# POWERREG.net
KiCad netlist of a schematic drawn in Altium Designer
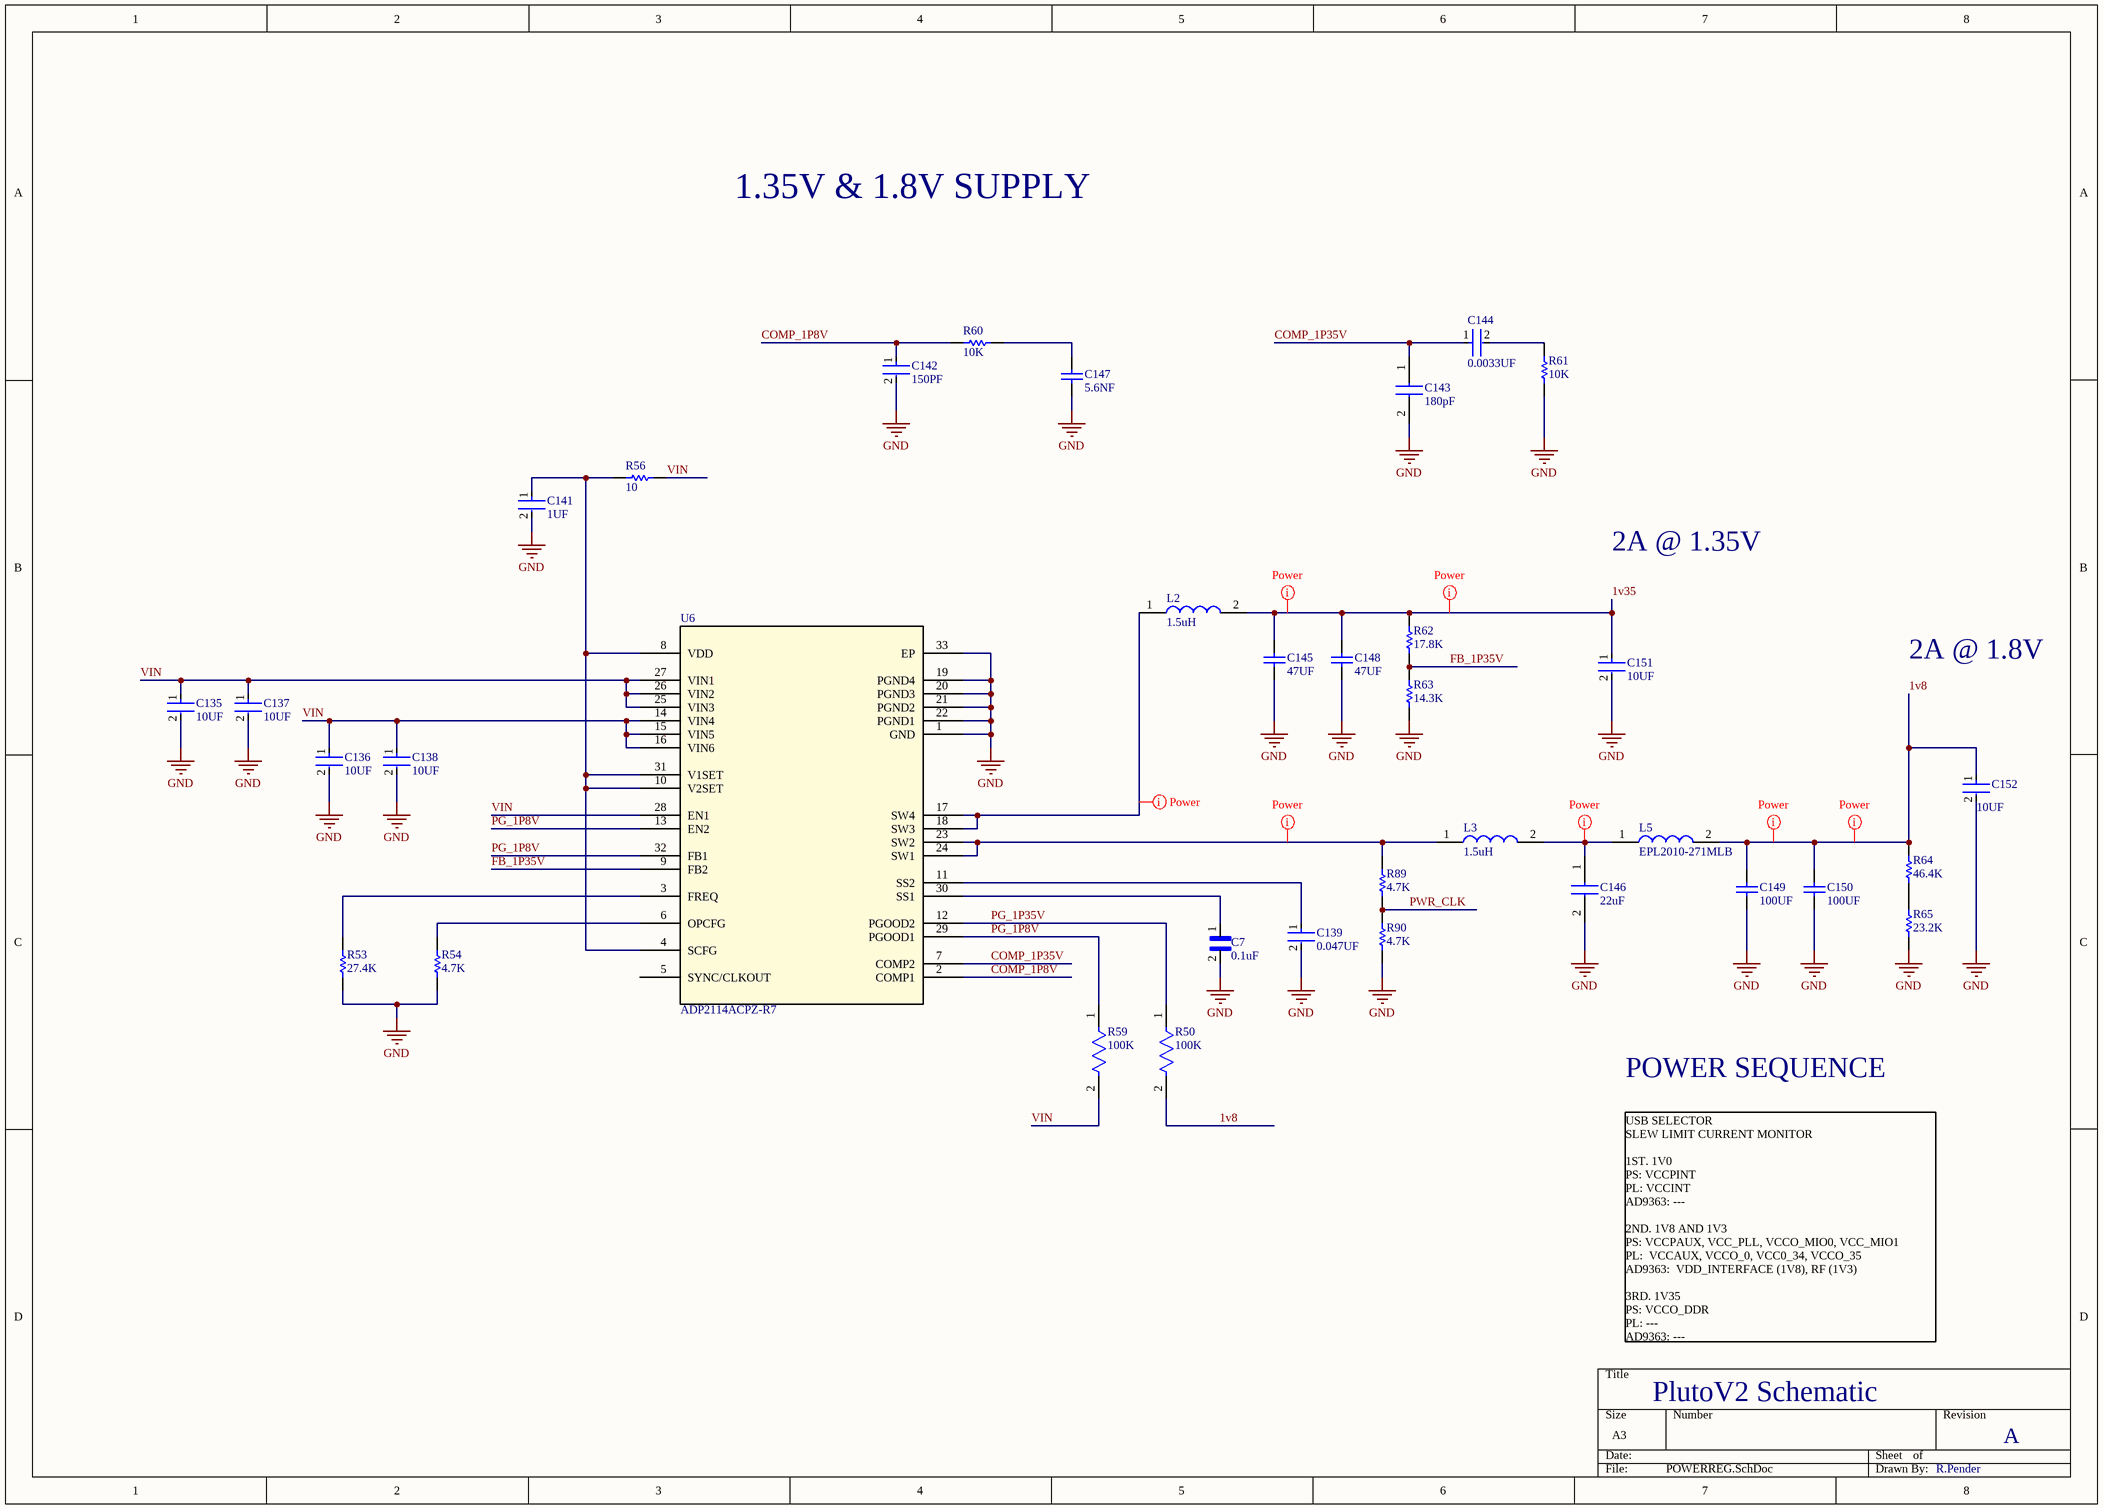
[diagram p0: POWERREG.SchDoc]

(export (version "E")
  (design (tool "Eeschema 10.0.6"))
  (components
    (comp (ref "C7")
      (value "0.1uF")
      (footprint "CAPC0603X33N")
      (description "CAP 0.1UF 16VDC X5R 20% SMD 0201 PAPER TAPE")
      (fields (field (name "MP") "GRM033R61C104ME84D"))
      (libsource (lib "GRM033R61C104ME84D") (part "GRM033R61C104ME84D"))
    )
    (comp (ref "C135")
      (value "10UF")
      (footprint "FP-GRM188-0_15-MFG")
      (description "Chip Multilayer Ceramic Capacitors for General Purpose, 0603, 10uF, X5R, 15%, 20%, 10V")
      (fields (field (name "TOLERANCE") "20%"))
      (libsource (lib "Altium Content Vault") (part "02cd4be3c70576c341d710602a673aa"))
    )
    (comp (ref "C136")
      (value "10UF")
      (footprint "FP-GRM188-0_15-MFG")
      (description "Chip Multilayer Ceramic Capacitors for General Purpose, 0603, 10uF, X5R, 15%, 20%, 10V")
      (fields (field (name "TOLERANCE") "20%"))
      (libsource (lib "Altium Content Vault") (part "02cd4be3c70576c341d710602a673aa"))
    )
    (comp (ref "C137")
      (value "10UF")
      (footprint "FP-GRM188-0_15-MFG")
      (description "Chip Multilayer Ceramic Capacitors for General Purpose, 0603, 10uF, X5R, 15%, 20%, 10V")
      (fields (field (name "TOLERANCE") "20%"))
      (libsource (lib "Altium Content Vault") (part "02cd4be3c70576c341d710602a673aa"))
    )
    (comp (ref "C138")
      (value "10UF")
      (footprint "FP-GRM188-0_15-MFG")
      (description "Chip Multilayer Ceramic Capacitors for General Purpose, 0603, 10uF, X5R, 15%, 20%, 10V")
      (fields (field (name "TOLERANCE") "20%"))
      (libsource (lib "Altium Content Vault") (part "02cd4be3c70576c341d710602a673aa"))
    )
    (comp (ref "C139")
      (value "0.047UF")
      (footprint "FP-GCM155-0_05-IPC_C")
      (description "Ceramic Capacitor for Automotive 47nF ±10% 25VDC X7R 0402 Paper T/R")
      (fields (field (name "VOLTAGE") "25V") (field (name "TOLERANCE") "10%"))
      (libsource (lib "Altium Content Vault") (part "02cd4be3c70576c341d710602a673aa"))
    )
    (comp (ref "C141")
      (value "1UF")
      (footprint "FP-0402-L_1_0_0_05-W_0_5-IPC_A")
      (description "None")
      (fields (field (name "TOLERANCE") "10%"))
      (libsource (lib "Altium Content Vault") (part "b4654b650e69147ec39a6b967a45e02"))
    )
    (comp (ref "C142")
      (value "150PF")
      (footprint "FP-GCM155-0_05-IPC_C")
      (description "Ceramic Capacitor for Automotive 150pF ±1% 50VDC C0G 0402 Paper T/R")
      (libsource (lib "Altium Content Vault") (part "02cd4be3c70576c341d710602a673aa"))
    )
    (comp (ref "C143")
      (value "180pF")
      (footprint "SamacSys:CAPC1005X55N")
      (description "Capacitor")
      (fields (field (name "MANUFACTURER_PART_NUMBER") "CGJ2B2C0G1H181J050BA"))
      (libsource (lib "SamacSys") (part "CGJ2B2C0G1H181J050BA"))
    )
    (comp (ref "C144")
      (value "0.0033UF")
      (footprint "FP-CC0402-MFG")
      (description "CAP CER 3300PF 50V X7R 0402")
      (fields
        (field (name "OCTOPART") "https://octopart.com/cc0402krx7r9bb332-yageo-192887")
        (field (name "MANUFACTURER") "YAGEO")
      )
      (libsource (lib "Altium Content Vault") (part "11868f565c42a9108669ba33697ecf6"))
    )
    (comp (ref "C145")
      (value "47UF")
      (footprint "TAYO-JMK212BBJ476MG-T_L")
      (fields
        (field (name "MANUFACTURER") "Taiyo Yuden")
        (field (name "TOLERANCE") "±20%")
        (field (name "PCN PART NUMBER") "X5R,X7RDielectrics23/Jan/2008")
      )
      (libsource (lib "Altium Content Vault") (part "CAP-NP-2"))
    )
    (comp (ref "C146")
      (value "22uF")
      (footprint "SamacSys:CAPC2012X95N")
      (description "Capacitor")
      (fields (field (name "MANUFACTURER_PART_NUMBER") "CL21A226KPCLRNC"))
      (libsource (lib "SamacSys") (part "CL21A226KPCLRNC"))
    )
    (comp (ref "C147")
      (value "5.6NF")
      (footprint "CAPC1005X56X25NL10T15")
      (fields
        (field (name "MANUFACTURER") "AVX Interconnect / Elco")
        (field (name "PART NUMBER") "04025C562JAT2A")
      )
      (libsource (lib "Altium Content Vault") (part "CAP"))
    )
    (comp (ref "C148")
      (value "47UF")
      (footprint "TAYO-JMK212BBJ476MG-T_L")
      (fields
        (field (name "MANUFACTURER") "Taiyo Yuden")
        (field (name "TOLERANCE") "±20%")
        (field (name "PCN PART NUMBER") "X5R,X7RDielectrics23/Jan/2008")
      )
      (libsource (lib "Altium Content Vault") (part "CAP-NP-2"))
    )
    (comp (ref "C149")
      (value "100UF")
      (footprint "CAPC3216X190X55ML30T25")
      (description "Chip Capacitor, 100 uF, +/- 20%, 6.3 V, -55 to 85 degC, 1206 (3216 Metric), RoHS, Tape and Reel")
      (fields (field (name "TOLERANCE") "20%") (field (name "PARTNUMBER") "GRM31CR60J107ME39L"))
      (libsource (lib "Altium Content Vault") (part "CAP-NP-2"))
    )
    (comp (ref "C150")
      (value "100UF")
      (footprint "CAPC3216X190X55ML30T25")
      (description "Chip Capacitor, 100 uF, +/- 20%, 6.3 V, -55 to 85 degC, 1206 (3216 Metric), RoHS, Tape and Reel")
      (fields (field (name "TOLERANCE") "20%") (field (name "PARTNUMBER") "GRM31CR60J107ME39L"))
      (libsource (lib "Altium Content Vault") (part "CAP-NP-2"))
    )
    (comp (ref "C151")
      (value "10UF")
      (footprint "FP-GRM188-0_1-e0_2_0_55-IPC_A")
      (description "Chip Multilayer Ceramic Capacitors for General Purpose, 0603, 10uF, X5R, 15%, 20%, 6.3V")
      (fields (field (name "VOLTAGE") "6.3V") (field (name "TOLERANCE") "20%"))
      (libsource (lib "Altium Content Vault") (part "02cd4be3c70576c341d710602a673aa"))
    )
    (comp (ref "C152")
      (value "10UF")
      (footprint "FP-GRM188-0_1-e0_2_0_55-IPC_A")
      (description "Chip Multilayer Ceramic Capacitors for General Purpose, 0603, 10uF, X5R, 15%, 20%, 6.3V")
      (fields (field (name "VOLTAGE") "6.3V") (field (name "TOLERANCE") "20%"))
      (libsource (lib "Altium Content Vault") (part "02cd4be3c70576c341d710602a673aa"))
    )
    (comp (ref "L2")
      (value "1.5uH")
      (footprint "SamacSys:XFL4020152MEB")
      (description "Inductor")
      (fields
        (field (name "MOUSER2 PART NUMBER") "994-XFL4020-152MEB")
        (field (name "MANUFACTURER_PART_NUMBER") "XFL4020-152MEB")
      )
      (libsource (lib "SamacSys") (part "XFL4020-152MEB"))
    )
    (comp (ref "L3")
      (value "1.5uH")
      (footprint "SamacSys:XFL4020152MEB")
      (description "Inductor")
      (fields
        (field (name "MOUSER2 PART NUMBER") "994-XFL4020-152MEB")
        (field (name "MANUFACTURER_PART_NUMBER") "XFL4020-152MEB")
      )
      (libsource (lib "SamacSys") (part "XFL4020-152MEB"))
    )
    (comp (ref "L5")
      (value "EPL2010-271MLB")
      (footprint "SamacSys:EPL2010271MLB")
      (description "Inductor")
      (libsource (lib "SamacSys") (part "EPL2010-271MLB"))
    )
    (comp (ref "R50")
      (value "100K")
      (footprint "FP-ERJ2RK-IPC_C")
      (description "RES SMD 100K OHM 1% 1/10W 0402")
      (fields (field (name "TOLERANCE") "1%"))
      (libsource (lib "Altium Content Vault") (part "1029c3af85768c4190bb7ad29bc67b5"))
    )
    (comp (ref "R53")
      (value "27.4K")
      (footprint "2-0402")
      (fields (field (name "PUBLISHER") "Altium Limited"))
      (libsource (lib "Panasonic Resistor") (part "ERJ2RK"))
    )
    (comp (ref "R54")
      (value "4.7K")
      (footprint "2-0402")
      (fields (field (name "PUBLISHER") "Altium Limited"))
      (libsource (lib "Panasonic Resistor") (part "ERJ2RK"))
    )
    (comp (ref "R56")
      (value "10")
      (footprint "RESC0603X26X15LL03T05")
      (fields (field (name "MANUFACTURER") "Panasonic") (field (name "PART NUMBER") "ERJ1GNF10R0C"))
      (libsource (lib "Altium Content Vault") (part "RES"))
    )
    (comp (ref "R59")
      (value "100K")
      (footprint "FP-ERJ2RK-IPC_C")
      (description "RES SMD 100K OHM 1% 1/10W 0402")
      (fields (field (name "TOLERANCE") "1%"))
      (libsource (lib "Altium Content Vault") (part "1029c3af85768c4190bb7ad29bc67b5"))
    )
    (comp (ref "R60")
      (value "10K")
      (footprint "2-0402")
      (fields (field (name "PUBLISHER") "Altium Limited"))
      (libsource (lib "Panasonic Resistor") (part "ERJ2RK"))
    )
    (comp (ref "R61")
      (value "10K")
      (footprint "2-0402")
      (fields (field (name "PUBLISHER") "Altium Limited"))
      (libsource (lib "Panasonic Resistor") (part "ERJ2RK"))
    )
    (comp (ref "R62")
      (value "17.8K")
      (footprint "3-0603")
      (fields (field (name "PUBLISHER") "Altium Limited"))
      (libsource (lib "Panasonic Resistor") (part "ERJ3EK"))
    )
    (comp (ref "R63")
      (value "14.3K")
      (footprint "3-0603")
      (fields (field (name "PUBLISHER") "Altium Limited"))
      (libsource (lib "Panasonic Resistor") (part "ERJ3EK"))
    )
    (comp (ref "R64")
      (value "46.4K")
      (footprint "2-0402")
      (fields (field (name "PUBLISHER") "Altium Limited"))
      (libsource (lib "Panasonic Resistor") (part "ERJ2RK"))
    )
    (comp (ref "R65")
      (value "23.2K")
      (footprint "2-0402")
      (fields (field (name "PUBLISHER") "Altium Limited"))
      (libsource (lib "Panasonic Resistor") (part "ERJ2RK"))
    )
    (comp (ref "R89")
      (value "4.7K")
      (footprint "2-0402")
      (fields (field (name "PUBLISHER") "Altium Limited"))
      (libsource (lib "Panasonic Resistor") (part "ERJ2RK"))
    )
    (comp (ref "R90")
      (value "4.7K")
      (footprint "2-0402")
      (fields (field (name "PUBLISHER") "Altium Limited"))
      (libsource (lib "Panasonic Resistor") (part "ERJ2RK"))
    )
    (comp (ref "U6")
      (value "ADP2114ACPZ-R7")
      (footprint "CP_32_2_ADI")
      (description "No Description Available")
      (fields (field (name "COPYRIGHT") "Copyright (C) 2022 Ultra Librarian. All rights reserved."))
      (libsource (lib "ADP2114ACPZ-R7") (part "ADP2114ACPZ-R7"))
    )
  )
  (nets
    (net (code "1") (name "/1v8") (class "Default")
      (node (ref "C149") (pin "1") (pinfunction "1_1") (pintype "passive"))
      (node (ref "C150") (pin "1") (pinfunction "1_1") (pintype "passive"))
      (node (ref "C152") (pin "1") (pinfunction "1_1") (pintype "passive"))
      (node (ref "L5") (pin "2") (pinfunction "2_2") (pintype "passive"))
      (node (ref "R50") (pin "2") (pinfunction "2_2") (pintype "passive"))
      (node (ref "R64") (pin "1") (pinfunction "1_1") (pintype "passive"))
    )
    (net (code "2") (name "/1v35") (class "Default")
      (node (ref "C145") (pin "1") (pinfunction "1_1") (pintype "passive"))
      (node (ref "C148") (pin "1") (pinfunction "1_1") (pintype "passive"))
      (node (ref "C151") (pin "1") (pinfunction "1_1") (pintype "passive"))
      (node (ref "L2") (pin "2") (pinfunction "2_2") (pintype "passive"))
      (node (ref "R62") (pin "1") (pinfunction "1_1") (pintype "passive"))
    )
    (net (code "3") (name "/COMP_1P8V") (class "Default")
      (node (ref "C142") (pin "1") (pinfunction "1_1") (pintype "passive"))
      (node (ref "R60") (pin "1") (pinfunction "1_1") (pintype "passive"))
      (node (ref "U6") (pin "2") (pinfunction "COMP1_2") (pintype "passive"))
    )
    (net (code "4") (name "/COMP_1P35V") (class "Default")
      (node (ref "C143") (pin "1") (pinfunction "1_1") (pintype "passive"))
      (node (ref "C144") (pin "1") (pinfunction "1_1") (pintype "passive"))
      (node (ref "U6") (pin "7") (pinfunction "COMP2_7") (pintype "passive"))
    )
    (net (code "5") (name "/FB_1P35V") (class "Default")
      (node (ref "R62") (pin "2") (pinfunction "2_2") (pintype "passive"))
      (node (ref "R63") (pin "1") (pinfunction "1_1") (pintype "passive"))
      (node (ref "U6") (pin "9") (pinfunction "FB2_9") (pintype "passive"))
    )
    (net (code "6") (name "/PG_1P8V") (class "Default")
      (node (ref "R59") (pin "1") (pinfunction "1_1") (pintype "passive"))
      (node (ref "U6") (pin "13") (pinfunction "EN2_13") (pintype "passive"))
      (node (ref "U6") (pin "29") (pinfunction "PGOOD1_29") (pintype "passive"))
      (node (ref "U6") (pin "32") (pinfunction "FB1_32") (pintype "passive"))
    )
    (net (code "7") (name "/PG_1P35V") (class "Default")
      (node (ref "R50") (pin "1") (pinfunction "1_1") (pintype "passive"))
      (node (ref "U6") (pin "12") (pinfunction "PGOOD2_12") (pintype "passive"))
    )
    (net (code "8") (name "/PWR_CLK") (class "Default")
      (node (ref "R89") (pin "2") (pinfunction "2_2") (pintype "passive"))
      (node (ref "R90") (pin "1") (pinfunction "1_1") (pintype "passive"))
    )
    (net (code "9") (name "/VIN") (class "Default")
      (node (ref "C135") (pin "1") (pinfunction "1_1") (pintype "passive"))
      (node (ref "C136") (pin "1") (pinfunction "1_1") (pintype "passive"))
      (node (ref "C137") (pin "1") (pinfunction "1_1") (pintype "passive"))
      (node (ref "C138") (pin "1") (pinfunction "1_1") (pintype "passive"))
      (node (ref "R56") (pin "2") (pinfunction "2_2") (pintype "passive"))
      (node (ref "R59") (pin "2") (pinfunction "2_2") (pintype "passive"))
      (node (ref "U6") (pin "14") (pinfunction "VIN4_14") (pintype "passive"))
      (node (ref "U6") (pin "15") (pinfunction "VIN5_15") (pintype "passive"))
      (node (ref "U6") (pin "16") (pinfunction "VIN6_16") (pintype "passive"))
      (node (ref "U6") (pin "25") (pinfunction "VIN3_25") (pintype "passive"))
      (node (ref "U6") (pin "26") (pinfunction "VIN2_26") (pintype "passive"))
      (node (ref "U6") (pin "27") (pinfunction "VIN1_27") (pintype "passive"))
      (node (ref "U6") (pin "28") (pinfunction "EN1_28") (pintype "passive"))
    )
    (net (code "10") (name "GND") (class "Default")
      (node (ref "C135") (pin "2") (pinfunction "2_2") (pintype "passive"))
      (node (ref "C136") (pin "2") (pinfunction "2_2") (pintype "passive"))
      (node (ref "C137") (pin "2") (pinfunction "2_2") (pintype "passive"))
      (node (ref "C138") (pin "2") (pinfunction "2_2") (pintype "passive"))
      (node (ref "C139") (pin "2") (pinfunction "2_2") (pintype "passive"))
      (node (ref "C141") (pin "2") (pinfunction "2_2") (pintype "passive"))
      (node (ref "C142") (pin "2") (pinfunction "2_2") (pintype "passive"))
      (node (ref "C143") (pin "2") (pinfunction "2_2") (pintype "passive"))
      (node (ref "C145") (pin "2") (pinfunction "2_2") (pintype "passive"))
      (node (ref "C146") (pin "2") (pinfunction "2_2") (pintype "passive"))
      (node (ref "C147") (pin "2") (pinfunction "2_2") (pintype "passive"))
      (node (ref "C148") (pin "2") (pinfunction "2_2") (pintype "passive"))
      (node (ref "C149") (pin "2") (pinfunction "2_2") (pintype "passive"))
      (node (ref "C150") (pin "2") (pinfunction "2_2") (pintype "passive"))
      (node (ref "C151") (pin "2") (pinfunction "2_2") (pintype "passive"))
      (node (ref "C152") (pin "2") (pinfunction "2_2") (pintype "passive"))
      (node (ref "C7") (pin "2") (pinfunction "2_2") (pintype "passive"))
      (node (ref "R53") (pin "2") (pinfunction "2_2") (pintype "passive"))
      (node (ref "R54") (pin "2") (pinfunction "2_2") (pintype "passive"))
      (node (ref "R61") (pin "2") (pinfunction "2_2") (pintype "passive"))
      (node (ref "R63") (pin "2") (pinfunction "2_2") (pintype "passive"))
      (node (ref "R65") (pin "2") (pinfunction "2_2") (pintype "passive"))
      (node (ref "R90") (pin "2") (pinfunction "2_2") (pintype "passive"))
      (node (ref "U6") (pin "1") (pinfunction "GND_1") (pintype "passive"))
      (node (ref "U6") (pin "19") (pinfunction "PGND4_19") (pintype "passive"))
      (node (ref "U6") (pin "20") (pinfunction "PGND3_20") (pintype "passive"))
      (node (ref "U6") (pin "21") (pinfunction "PGND2_21") (pintype "passive"))
      (node (ref "U6") (pin "22") (pinfunction "PGND1_22") (pintype "passive"))
      (node (ref "U6") (pin "33") (pinfunction "EP_33") (pintype "passive"))
    )
    (net (code "11") (name "Net-(C144-Pad2)") (class "Default")
      (node (ref "C144") (pin "2") (pinfunction "2_2") (pintype "passive"))
      (node (ref "R61") (pin "1") (pinfunction "1_1") (pintype "passive"))
    )
    (net (code "12") (name "Net-(C146-Pad1)") (class "Default")
      (node (ref "C146") (pin "1") (pinfunction "1_1") (pintype "passive"))
      (node (ref "L3") (pin "2") (pinfunction "2_2") (pintype "passive"))
      (node (ref "L5") (pin "1") (pinfunction "1_1") (pintype "passive"))
    )
    (net (code "13") (name "Net-(C147-Pad1)") (class "Default")
      (node (ref "C147") (pin "1") (pinfunction "1_1") (pintype "passive"))
      (node (ref "R60") (pin "2") (pinfunction "2_2") (pintype "passive"))
    )
    (net (code "14") (name "Net-(R64-Pad2)") (class "Default")
      (node (ref "R64") (pin "2") (pinfunction "2_2") (pintype "passive"))
      (node (ref "R65") (pin "1") (pinfunction "1_1") (pintype "passive"))
    )
    (net (code "15") (name "Net-(U6-FREQ)") (class "Default")
      (node (ref "R53") (pin "1") (pinfunction "1_1") (pintype "passive"))
      (node (ref "U6") (pin "3") (pinfunction "FREQ_3") (pintype "passive"))
    )
    (net (code "16") (name "Net-(U6-OPCFG)") (class "Default")
      (node (ref "R54") (pin "1") (pinfunction "1_1") (pintype "passive"))
      (node (ref "U6") (pin "6") (pinfunction "OPCFG_6") (pintype "passive"))
    )
    (net (code "17") (name "Net-(U6-SCFG)") (class "Default")
      (node (ref "C141") (pin "1") (pinfunction "1_1") (pintype "passive"))
      (node (ref "R56") (pin "1") (pinfunction "1_1") (pintype "passive"))
      (node (ref "U6") (pin "10") (pinfunction "V2SET_10") (pintype "passive"))
      (node (ref "U6") (pin "31") (pinfunction "V1SET_31") (pintype "passive"))
      (node (ref "U6") (pin "4") (pinfunction "SCFG_4") (pintype "passive"))
      (node (ref "U6") (pin "8") (pinfunction "VDD_8") (pintype "passive"))
    )
    (net (code "18") (name "Net-(U6-SS1)") (class "Default")
      (node (ref "C7") (pin "1") (pinfunction "1_1") (pintype "passive"))
      (node (ref "U6") (pin "30") (pinfunction "SS1_30") (pintype "passive"))
    )
    (net (code "19") (name "Net-(U6-SS2)") (class "Default")
      (node (ref "C139") (pin "1") (pinfunction "1_1") (pintype "passive"))
      (node (ref "U6") (pin "11") (pinfunction "SS2_11") (pintype "passive"))
    )
    (net (code "20") (name "Net-(U6-SW1)") (class "Default")
      (node (ref "L3") (pin "1") (pinfunction "1_1") (pintype "passive"))
      (node (ref "R89") (pin "1") (pinfunction "1_1") (pintype "passive"))
      (node (ref "U6") (pin "23") (pinfunction "SW2_23") (pintype "passive"))
      (node (ref "U6") (pin "24") (pinfunction "SW1_24") (pintype "passive"))
    )
    (net (code "21") (name "Net-(U6-SW3)") (class "Default")
      (node (ref "L2") (pin "1") (pinfunction "1_1") (pintype "passive"))
      (node (ref "U6") (pin "17") (pinfunction "SW4_17") (pintype "passive"))
      (node (ref "U6") (pin "18") (pinfunction "SW3_18") (pintype "passive"))
    )
    (net (code "22") (name "unconnected-(U6-SYNC{slash}CLKOUT-Pad5)") (class "Default")
      (node (ref "U6") (pin "5") (pinfunction "SYNC/CLKOUT_5") (pintype "passive"))
    )
  )
)
